# untitled.net
KiCad netlist of a schematic drawn in EAGLE
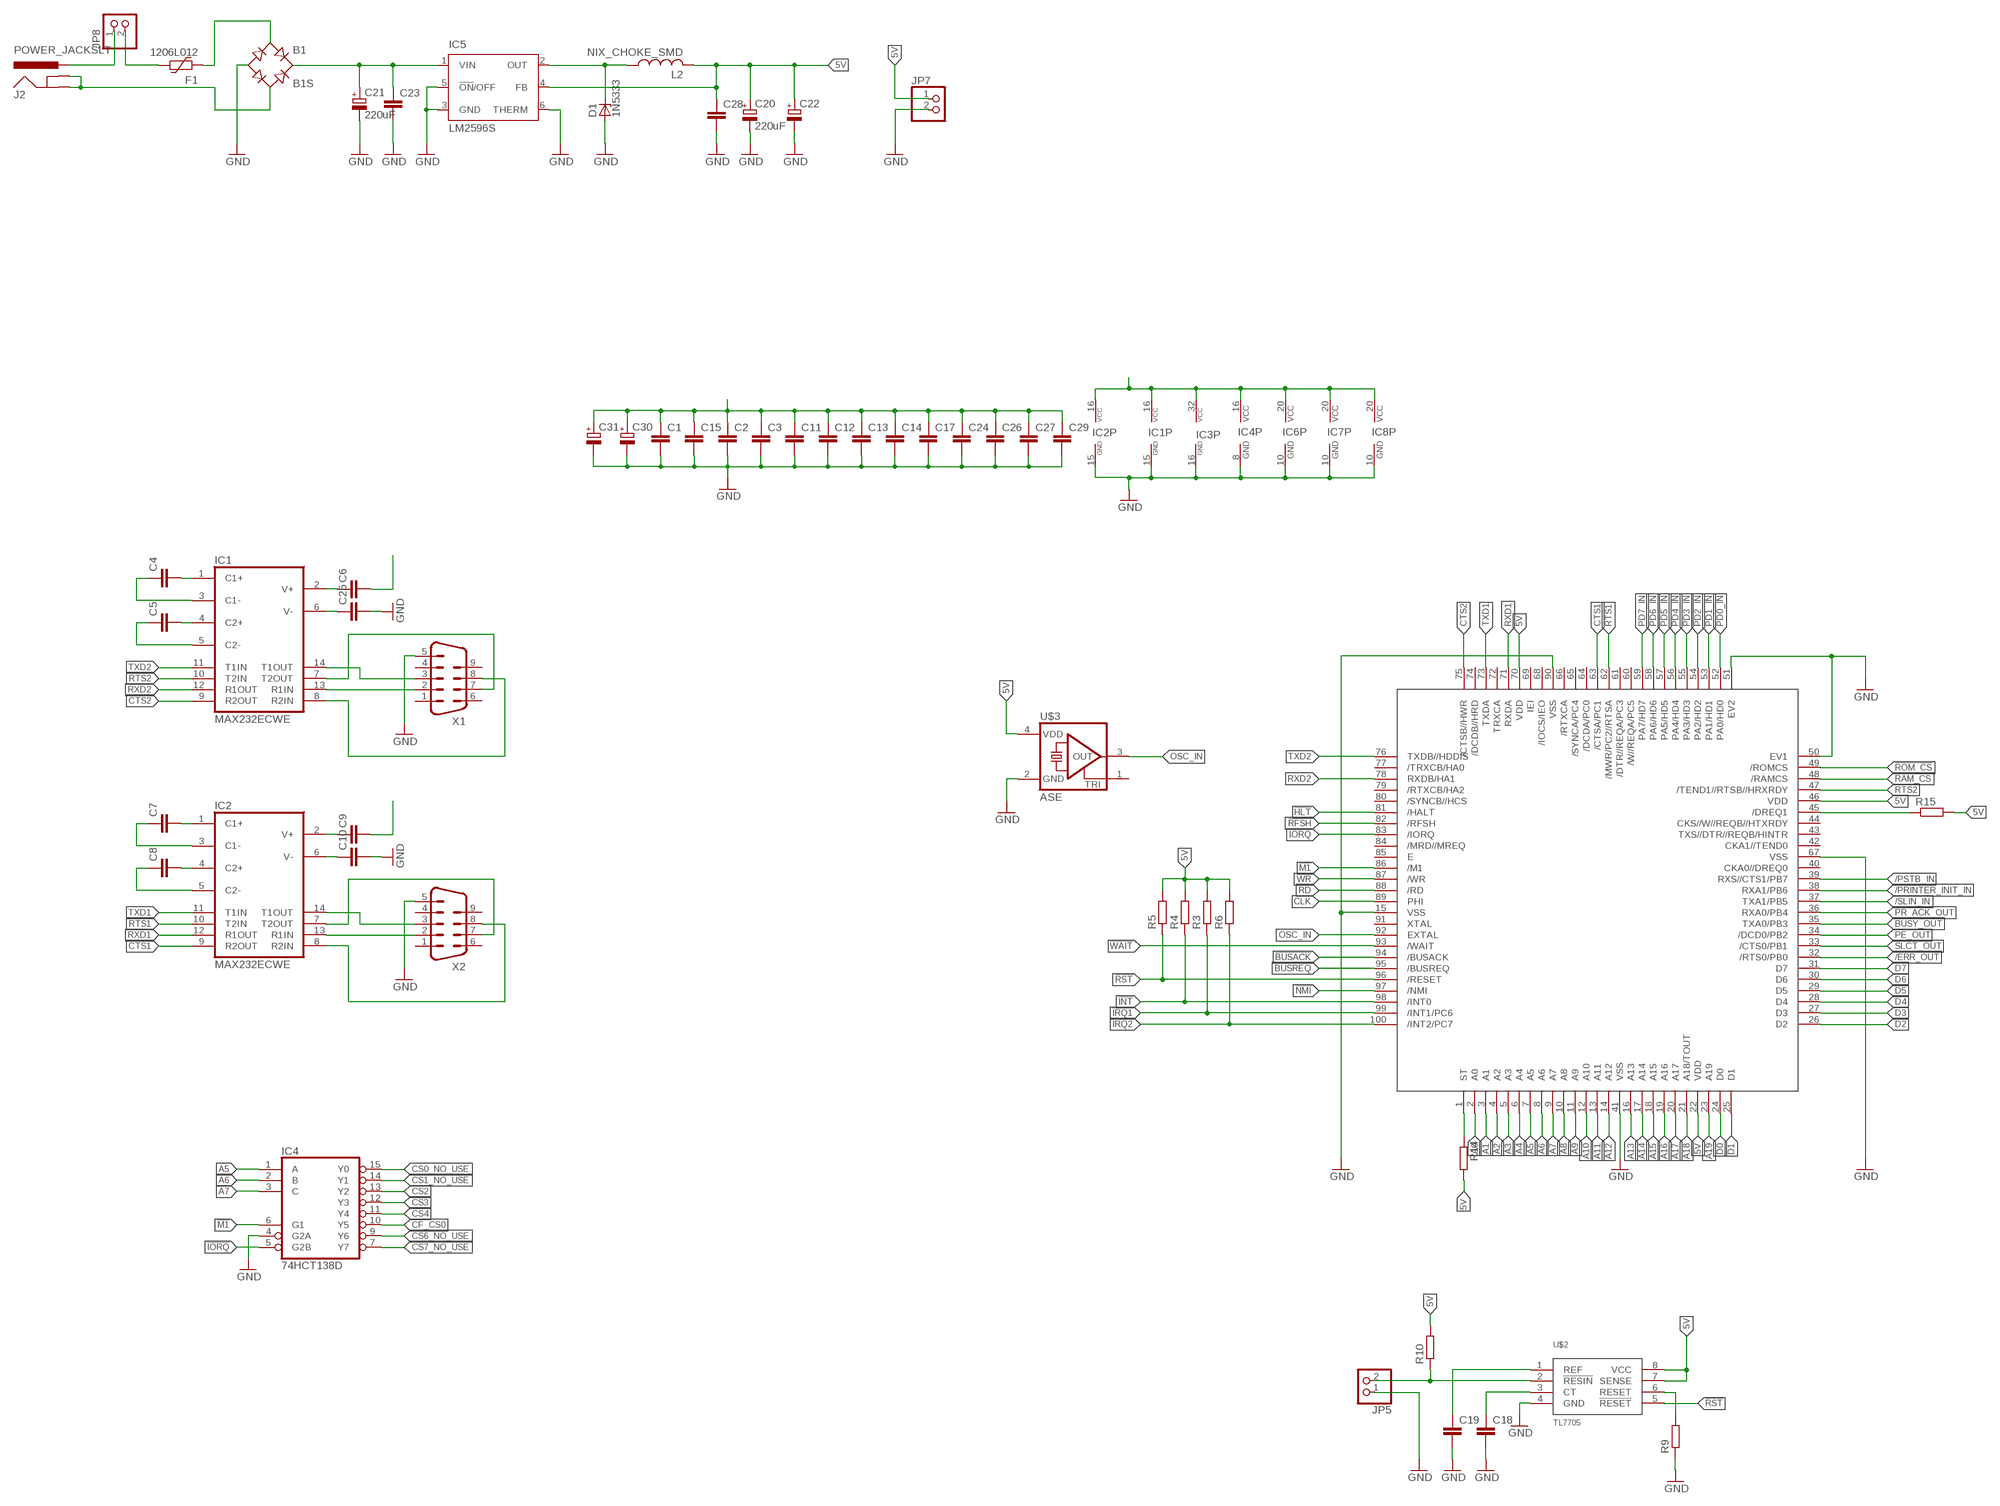
[diagram p0: schematic, sheet 1, part 1 of 2]
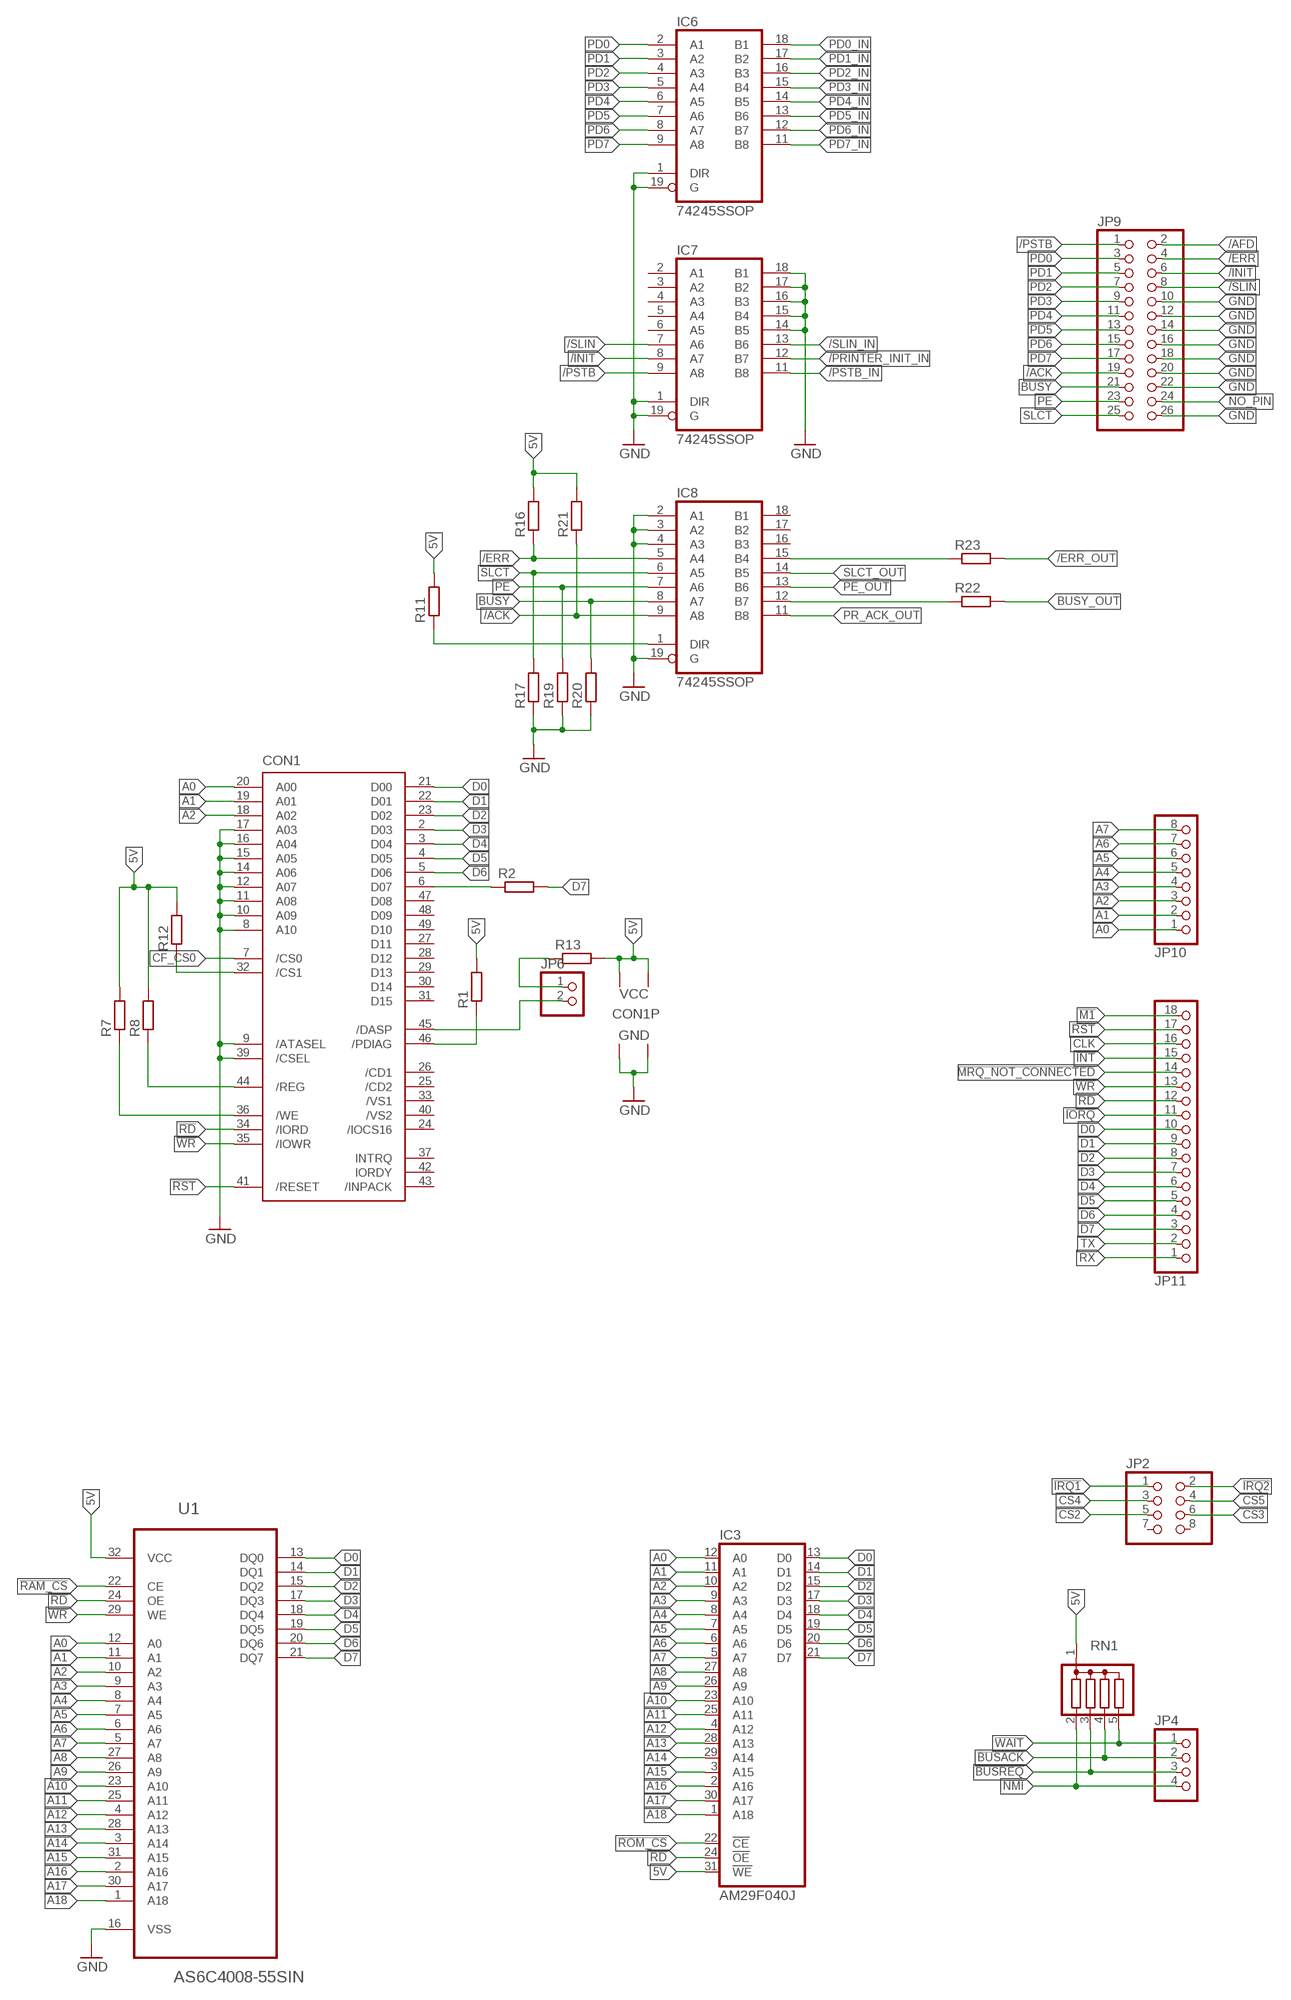
[diagram p1: schematic, sheet 1, part 2 of 2]

(export (version "E")
  (design (tool "Eeschema 10.0.6"))
  (components
    (comp (ref "B1")
      (value "B1S")
      (footprint "eagle-import:MBS")
      (libsource (lib "eagle-import") (part "BS1"))
    )
    (comp (ref "C1")
      (value "C-EUC0603")
      (footprint "eagle-import:C0603")
      (libsource (lib "eagle-import") (part "C-EUC0603"))
    )
    (comp (ref "C2")
      (value "C-EUC0603")
      (footprint "eagle-import:C0603")
      (libsource (lib "eagle-import") (part "C-EUC0603"))
    )
    (comp (ref "C3")
      (value "C-EUC0402")
      (footprint "eagle-import:C0402")
      (libsource (lib "eagle-import") (part "C-EUC0402"))
    )
    (comp (ref "C4")
      (value "C-EUC0603")
      (footprint "eagle-import:C0603")
      (libsource (lib "eagle-import") (part "C-EUC0603"))
    )
    (comp (ref "C5")
      (value "C-EUC0603")
      (footprint "eagle-import:C0603")
      (libsource (lib "eagle-import") (part "C-EUC0603"))
    )
    (comp (ref "C6")
      (value "C-EUC0603")
      (footprint "eagle-import:C0603")
      (libsource (lib "eagle-import") (part "C-EUC0603"))
    )
    (comp (ref "C7")
      (value "C-EUC0603")
      (footprint "eagle-import:C0603")
      (libsource (lib "eagle-import") (part "C-EUC0603"))
    )
    (comp (ref "C8")
      (value "C-EUC0603")
      (footprint "eagle-import:C0603")
      (libsource (lib "eagle-import") (part "C-EUC0603"))
    )
    (comp (ref "C9")
      (value "C-EUC0603")
      (footprint "eagle-import:C0603")
      (libsource (lib "eagle-import") (part "C-EUC0603"))
    )
    (comp (ref "C10")
      (value "C-EUC0603")
      (footprint "eagle-import:C0603")
      (libsource (lib "eagle-import") (part "C-EUC0603"))
    )
    (comp (ref "C11")
      (value "C-EUC0603")
      (footprint "eagle-import:C0603")
      (libsource (lib "eagle-import") (part "C-EUC0603"))
    )
    (comp (ref "C12")
      (value "C-EUC0603")
      (footprint "eagle-import:C0603")
      (libsource (lib "eagle-import") (part "C-EUC0603"))
    )
    (comp (ref "C13")
      (value "C-EUC0402")
      (footprint "eagle-import:C0402")
      (libsource (lib "eagle-import") (part "C-EUC0402"))
    )
    (comp (ref "C14")
      (value "C-EUC0603")
      (footprint "eagle-import:C0603")
      (libsource (lib "eagle-import") (part "C-EUC0603"))
    )
    (comp (ref "C15")
      (value "C-EUC0603")
      (footprint "eagle-import:C0603")
      (libsource (lib "eagle-import") (part "C-EUC0603"))
    )
    (comp (ref "C17")
      (value "C-EUC0603")
      (footprint "eagle-import:C0603")
      (libsource (lib "eagle-import") (part "C-EUC0603"))
    )
    (comp (ref "C18")
      (value "C-EUC0603")
      (footprint "eagle-import:C0603")
      (libsource (lib "eagle-import") (part "C-EUC0603"))
    )
    (comp (ref "C19")
      (value "C-EUC0603")
      (footprint "eagle-import:C0603")
      (libsource (lib "eagle-import") (part "C-EUC0603"))
    )
    (comp (ref "C20")
      (value "220uF")
      (footprint "eagle-import:153CLV-0810")
      (libsource (lib "eagle-import") (part "CPOL-EU153CLV-0810"))
    )
    (comp (ref "C21")
      (value "220uF")
      (footprint "eagle-import:153CLV-0810")
      (libsource (lib "eagle-import") (part "CPOL-EU153CLV-0810"))
    )
    (comp (ref "C22")
      (value "CPOL-EUSMCC")
      (footprint "eagle-import:SMC_C")
      (libsource (lib "eagle-import") (part "CPOL-EUSMCC"))
    )
    (comp (ref "C23")
      (value "C-EUC0603")
      (footprint "eagle-import:C0603")
      (libsource (lib "eagle-import") (part "C-EUC0603"))
    )
    (comp (ref "C24")
      (value "C-EUC0603")
      (footprint "eagle-import:C0603")
      (libsource (lib "eagle-import") (part "C-EUC0603"))
    )
    (comp (ref "C25")
      (value "C-EUC0603")
      (footprint "eagle-import:C0603")
      (libsource (lib "eagle-import") (part "C-EUC0603"))
    )
    (comp (ref "C26")
      (value "C-EUC0402")
      (footprint "eagle-import:C0402")
      (libsource (lib "eagle-import") (part "C-EUC0402"))
    )
    (comp (ref "C27")
      (value "C-EUC0402")
      (footprint "eagle-import:C0402")
      (libsource (lib "eagle-import") (part "C-EUC0402"))
    )
    (comp (ref "C28")
      (value "C-EUC0603")
      (footprint "eagle-import:C0603")
      (libsource (lib "eagle-import") (part "C-EUC0603"))
    )
    (comp (ref "C29")
      (value "C-EUC0603")
      (footprint "eagle-import:C0603")
      (libsource (lib "eagle-import") (part "C-EUC0603"))
    )
    (comp (ref "C30")
      (value "CPOL-EUSMCB")
      (footprint "eagle-import:SMC_B")
      (libsource (lib "eagle-import") (part "CPOL-EUSMCB"))
    )
    (comp (ref "C31")
      (value "CPOL-EUSMCB")
      (footprint "eagle-import:SMC_B")
      (libsource (lib "eagle-import") (part "CPOL-EUSMCB"))
    )
    (comp (ref "CON1")
      (value "CF-CARD-IDE_MODE")
      (footprint "eagle-import:MI20-50PD-SF")
      (libsource (lib "eagle-import") (part "CF-CARD-IDE_MODE"))
    )
    (comp (ref "D1")
      (value "1N5333")
      (footprint "eagle-import:C1702-15")
      (libsource (lib "eagle-import") (part "1N5333"))
    )
    (comp (ref "F1")
      (value "1206L012")
      (footprint "eagle-import:1206L")
      (fields (field (name "MF") "Littelfuse"))
      (libsource (lib "eagle-import") (part "?1206L012"))
    )
    (comp (ref "IC1")
      (value "MAX232ECWE")
      (footprint "eagle-import:SO16L")
      (fields (field (name "MF") "MAXIM") (field (name "MPN") "MAX232ECWE+"))
      (libsource (lib "eagle-import") (part "MAX232ECWE"))
    )
    (comp (ref "IC2")
      (value "MAX232ECWE")
      (footprint "eagle-import:SO16L")
      (fields (field (name "MF") "MAXIM") (field (name "MPN") "MAX232ECWE+"))
      (libsource (lib "eagle-import") (part "MAX232ECWE"))
    )
    (comp (ref "IC3")
      (value "AM29F040J")
      (footprint "eagle-import:PLCC32R")
      (libsource (lib "eagle-import") (part "AM29F040J"))
    )
    (comp (ref "IC4")
      (value "74HCT138D")
      (footprint "eagle-import:SO16")
      (libsource (lib "eagle-import") (part "74138DHCT"))
    )
    (comp (ref "IC5")
      (value "LM2596S")
      (footprint "eagle-import:TO263-5")
      (fields (field (name "MF") "NATIONAL SEMICONDUCTOR") (field (name "MPN") "LM2596S-ADJ/NOPB"))
      (libsource (lib "eagle-import") (part "LM2596S"))
    )
    (comp (ref "IC6")
      (value "74245SSOP")
      (footprint "eagle-import:SSOP20")
      (libsource (lib "eagle-import") (part "74245SSOP"))
    )
    (comp (ref "IC7")
      (value "74245SSOP")
      (footprint "eagle-import:SSOP20")
      (libsource (lib "eagle-import") (part "74245SSOP"))
    )
    (comp (ref "IC8")
      (value "74245SSOP")
      (footprint "eagle-import:SSOP20")
      (libsource (lib "eagle-import") (part "74245SSOP"))
    )
    (comp (ref "J2")
      (value "POWER_JACKSLT")
      (footprint "eagle-import:POWER_JACK_SLOT")
      (libsource (lib "eagle-import") (part "POWER_JACKSLT"))
    )
    (comp (ref "JP2")
      (value "PINHD-2X4")
      (footprint "eagle-import:2X04")
      (libsource (lib "eagle-import") (part "PINHD-2X4"))
    )
    (comp (ref "JP4")
      (value "PINHD-1X4")
      (footprint "eagle-import:1X04")
      (libsource (lib "eagle-import") (part "PINHD-1X4"))
    )
    (comp (ref "JP5")
      (value "PINHD-1X2")
      (footprint "eagle-import:1X02")
      (libsource (lib "eagle-import") (part "PINHD-1X2"))
    )
    (comp (ref "JP6")
      (value "PINHD-1X2")
      (footprint "eagle-import:1X02")
      (libsource (lib "eagle-import") (part "PINHD-1X2"))
    )
    (comp (ref "JP7")
      (value "PINHD-1X2")
      (footprint "eagle-import:1X02")
      (libsource (lib "eagle-import") (part "PINHD-1X2"))
    )
    (comp (ref "JP8")
      (value "PINHD-1X2")
      (footprint "eagle-import:1X02")
      (libsource (lib "eagle-import") (part "PINHD-1X2"))
    )
    (comp (ref "JP9")
      (value "PINHD-2X13_2.54-SMD")
      (footprint "eagle-import:2X13SMD")
      (libsource (lib "eagle-import") (part "PINHD-2X13_2.54-SMD"))
    )
    (comp (ref "JP10")
      (value "PINHD-1X8")
      (footprint "eagle-import:1X08")
      (libsource (lib "eagle-import") (part "PINHD-1X8"))
    )
    (comp (ref "JP11")
      (value "PINHD-1X18")
      (footprint "eagle-import:1X18")
      (libsource (lib "eagle-import") (part "PINHD-1X18"))
    )
    (comp (ref "L2")
      (value "NIX_CHOKE_SMD")
      (footprint "eagle-import:NIX_CHOKE_SMD")
      (libsource (lib "eagle-import") (part "NIX_CHOKE_SMD"))
    )
    (comp (ref "R1")
      (value "R-EU_R0603")
      (footprint "eagle-import:R0603")
      (libsource (lib "eagle-import") (part "R-EU_R0603"))
    )
    (comp (ref "R2")
      (value "R-EU_R0603")
      (footprint "eagle-import:R0603")
      (libsource (lib "eagle-import") (part "R-EU_R0603"))
    )
    (comp (ref "R3")
      (value "R-EU_R0402")
      (footprint "eagle-import:R0402")
      (libsource (lib "eagle-import") (part "R-EU_R0402"))
    )
    (comp (ref "R4")
      (value "R-EU_R0603")
      (footprint "eagle-import:R0603")
      (libsource (lib "eagle-import") (part "R-EU_R0603"))
    )
    (comp (ref "R5")
      (value "R-EU_R1206")
      (footprint "eagle-import:R1206")
      (libsource (lib "eagle-import") (part "R-EU_R1206"))
    )
    (comp (ref "R6")
      (value "R-EU_R0603")
      (footprint "eagle-import:R0603")
      (libsource (lib "eagle-import") (part "R-EU_R0603"))
    )
    (comp (ref "R7")
      (value "R-EU_R0603")
      (footprint "eagle-import:R0603")
      (libsource (lib "eagle-import") (part "R-EU_R0603"))
    )
    (comp (ref "R8")
      (value "R-EU_R0603")
      (footprint "eagle-import:R0603")
      (libsource (lib "eagle-import") (part "R-EU_R0603"))
    )
    (comp (ref "R9")
      (value "R-EU_R0603")
      (footprint "eagle-import:R0603")
      (libsource (lib "eagle-import") (part "R-EU_R0603"))
    )
    (comp (ref "R10")
      (value "R-EU_M1206")
      (footprint "eagle-import:M1206")
      (libsource (lib "eagle-import") (part "R-EU_M1206"))
    )
    (comp (ref "R11")
      (value "R-EU_R0603")
      (footprint "eagle-import:R0603")
      (libsource (lib "eagle-import") (part "R-EU_R0603"))
    )
    (comp (ref "R12")
      (value "R-EU_R0603")
      (footprint "eagle-import:R0603")
      (libsource (lib "eagle-import") (part "R-EU_R0603"))
    )
    (comp (ref "R13")
      (value "R-EU_R0603")
      (footprint "eagle-import:R0603")
      (libsource (lib "eagle-import") (part "R-EU_R0603"))
    )
    (comp (ref "R14")
      (value "R-EU_0204/5")
      (footprint "eagle-import:0204_5")
      (libsource (lib "eagle-import") (part "R-EU_0204/5"))
    )
    (comp (ref "R15")
      (value "R-EU_R0402")
      (footprint "eagle-import:R0402")
      (libsource (lib "eagle-import") (part "R-EU_R0402"))
    )
    (comp (ref "R16")
      (value "R-EU_R0603")
      (footprint "eagle-import:R0603")
      (libsource (lib "eagle-import") (part "R-EU_R0603"))
    )
    (comp (ref "R17")
      (value "R-EU_R0603")
      (footprint "eagle-import:R0603")
      (libsource (lib "eagle-import") (part "R-EU_R0603"))
    )
    (comp (ref "R19")
      (value "R-EU_R0603")
      (footprint "eagle-import:R0603")
      (libsource (lib "eagle-import") (part "R-EU_R0603"))
    )
    (comp (ref "R20")
      (value "R-EU_R0603")
      (footprint "eagle-import:R0603")
      (libsource (lib "eagle-import") (part "R-EU_R0603"))
    )
    (comp (ref "R21")
      (value "R-EU_R0603")
      (footprint "eagle-import:R0603")
      (libsource (lib "eagle-import") (part "R-EU_R0603"))
    )
    (comp (ref "R22")
      (value "R-EU_R0402")
      (footprint "eagle-import:R0402")
      (libsource (lib "eagle-import") (part "R-EU_R0402"))
    )
    (comp (ref "R23")
      (value "R-EU_R0402")
      (footprint "eagle-import:R0402")
      (libsource (lib "eagle-import") (part "R-EU_R0402"))
    )
    (comp (ref "RN1")
      (value "G04R")
      (footprint "eagle-import:SIL5")
      (libsource (lib "eagle-import") (part "G04R"))
    )
    (comp (ref "U$1")
      (value "Z80182")
      (footprint "eagle-import:TQFP100")
      (libsource (lib "eagle-import") (part "Z80182"))
    )
    (comp (ref "U$2")
      (value "TL7705")
      (footprint "eagle-import:SOIC8")
      (libsource (lib "eagle-import") (part "TL7705"))
    )
    (comp (ref "U$3")
      (value "ASE")
      (footprint "eagle-import:ASE")
      (libsource (lib "eagle-import") (part "ASE"))
    )
    (comp (ref "U1")
      (value "AS6C4008-55SIN")
      (footprint "eagle-import:SOIC127P1407X299-32N")
      (libsource (lib "eagle-import") (part "AS6C4008-55SIN"))
    )
    (comp (ref "X1")
      (value "M09HP")
      (footprint "eagle-import:M09HP")
      (libsource (lib "eagle-import") (part "M09HP"))
    )
    (comp (ref "X2")
      (value "M09HP")
      (footprint "eagle-import:M09HP")
      (libsource (lib "eagle-import") (part "M09HP"))
    )
  )
  (nets
    (net (code "1") (name "/~{BUSACK}") (class "Default")
      (node (ref "JP4") (pin "2") (pinfunction "2_2") (pintype "passive"))
      (node (ref "RN1") (pin "4") (pinfunction "4_4") (pintype "passive"))
      (node (ref "U$1") (pin "94") (pinfunction "/BUSACK_94") (pintype "bidirectional"))
    )
    (net (code "2") (name "/~{BUSREQ}") (class "Default")
      (node (ref "JP4") (pin "3") (pinfunction "3_3") (pintype "passive"))
      (node (ref "RN1") (pin "3") (pinfunction "3_3") (pintype "passive"))
      (node (ref "U$1") (pin "95") (pinfunction "/BUSREQ_95") (pintype "bidirectional"))
    )
    (net (code "3") (name "/~{HLT}") (class "Default")
      (node (ref "U$1") (pin "81") (pinfunction "/HALT_81") (pintype "bidirectional"))
    )
    (net (code "4") (name "/~{INT}") (class "Default")
      (node (ref "JP11") (pin "15") (pinfunction "15_15") (pintype "passive"))
      (node (ref "R4") (pin "1") (pinfunction "1_1") (pintype "passive"))
      (node (ref "U$1") (pin "98") (pinfunction "/INT0_98") (pintype "bidirectional"))
    )
    (net (code "5") (name "/~{IORQ}") (class "Default")
      (node (ref "IC4") (pin "5") (pinfunction "G2B_5") (pintype "input"))
      (node (ref "JP11") (pin "11") (pinfunction "11_11") (pintype "passive"))
      (node (ref "U$1") (pin "83") (pinfunction "/IORQ_83") (pintype "bidirectional"))
    )
    (net (code "6") (name "/~{IRQ1}") (class "Default")
      (node (ref "JP2") (pin "1") (pinfunction "1_1") (pintype "passive"))
      (node (ref "R3") (pin "1") (pinfunction "1_1") (pintype "passive"))
      (node (ref "U$1") (pin "99") (pinfunction "/INT1/PC6_99") (pintype "bidirectional"))
    )
    (net (code "7") (name "/~{IRQ2}") (class "Default")
      (node (ref "JP2") (pin "2") (pinfunction "2_2") (pintype "passive"))
      (node (ref "R6") (pin "1") (pinfunction "1_1") (pintype "passive"))
      (node (ref "U$1") (pin "100") (pinfunction "/INT2/PC7_100") (pintype "bidirectional"))
    )
    (net (code "8") (name "/~{M1}") (class "Default")
      (node (ref "IC4") (pin "6") (pinfunction "G1_6") (pintype "input"))
      (node (ref "JP11") (pin "18") (pinfunction "18_18") (pintype "passive"))
      (node (ref "U$1") (pin "86") (pinfunction "/M1_86") (pintype "bidirectional"))
    )
    (net (code "9") (name "/~{MRQ_NOT_CONNECTED}") (class "Default")
      (node (ref "JP11") (pin "14") (pinfunction "14_14") (pintype "passive"))
    )
    (net (code "10") (name "/~{NMI}") (class "Default")
      (node (ref "JP4") (pin "4") (pinfunction "4_4") (pintype "passive"))
      (node (ref "RN1") (pin "2") (pinfunction "2_2") (pintype "passive"))
      (node (ref "U$1") (pin "97") (pinfunction "/NMI_97") (pintype "bidirectional"))
    )
    (net (code "11") (name "/~{RAM_CS}") (class "Default")
      (node (ref "U$1") (pin "48") (pinfunction "/RAMCS_48") (pintype "bidirectional"))
      (node (ref "U1") (pin "22") (pinfunction "CE_22") (pintype "input"))
    )
    (net (code "12") (name "/~{RD}") (class "Default")
      (node (ref "CON1") (pin "34") (pinfunction "/IORD_34") (pintype "input"))
      (node (ref "IC3") (pin "24") (pinfunction "~{OE}_24") (pintype "input"))
      (node (ref "JP11") (pin "12") (pinfunction "12_12") (pintype "passive"))
      (node (ref "U$1") (pin "88") (pinfunction "/RD_88") (pintype "bidirectional"))
      (node (ref "U1") (pin "24") (pinfunction "OE_24") (pintype "input"))
    )
    (net (code "13") (name "/~{RFSH}") (class "Default")
      (node (ref "U$1") (pin "82") (pinfunction "/RFSH_82") (pintype "bidirectional"))
    )
    (net (code "14") (name "/~{ROM_CS}") (class "Default")
      (node (ref "IC3") (pin "22") (pinfunction "~{CE}_22") (pintype "input"))
      (node (ref "U$1") (pin "49") (pinfunction "/ROMCS_49") (pintype "bidirectional"))
    )
    (net (code "15") (name "/~{RST}") (class "Default")
      (node (ref "CON1") (pin "41") (pinfunction "/RESET_41") (pintype "input"))
      (node (ref "JP11") (pin "17") (pinfunction "17_17") (pintype "passive"))
      (node (ref "R5") (pin "1") (pinfunction "1_1") (pintype "passive"))
      (node (ref "U$1") (pin "96") (pinfunction "/RESET_96") (pintype "bidirectional"))
      (node (ref "U$2") (pin "5") (pinfunction "~{RESET}_5") (pintype "bidirectional"))
    )
    (net (code "16") (name "/~{WAIT}") (class "Default")
      (node (ref "JP4") (pin "1") (pinfunction "1_1") (pintype "passive"))
      (node (ref "RN1") (pin "5") (pinfunction "5_5") (pintype "passive"))
      (node (ref "U$1") (pin "93") (pinfunction "/WAIT_93") (pintype "bidirectional"))
    )
    (net (code "17") (name "/~{WR}") (class "Default")
      (node (ref "CON1") (pin "35") (pinfunction "/IOWR_35") (pintype "input"))
      (node (ref "JP11") (pin "13") (pinfunction "13_13") (pintype "passive"))
      (node (ref "U$1") (pin "87") (pinfunction "/WR_87") (pintype "bidirectional"))
      (node (ref "U1") (pin "29") (pinfunction "WE_29") (pintype "input"))
    )
    (net (code "18") (name "5V") (class "Default")
      (node (ref "C1") (pin "1") (pinfunction "1_1") (pintype "passive"))
      (node (ref "C11") (pin "1") (pinfunction "1_1") (pintype "passive"))
      (node (ref "C12") (pin "1") (pinfunction "1_1") (pintype "passive"))
      (node (ref "C13") (pin "1") (pinfunction "1_1") (pintype "passive"))
      (node (ref "C14") (pin "1") (pinfunction "1_1") (pintype "passive"))
      (node (ref "C15") (pin "1") (pinfunction "1_1") (pintype "passive"))
      (node (ref "C17") (pin "1") (pinfunction "1_1") (pintype "passive"))
      (node (ref "C2") (pin "1") (pinfunction "1_1") (pintype "passive"))
      (node (ref "C20") (pin "+") (pinfunction "+_+") (pintype "passive"))
      (node (ref "C22") (pin "+") (pinfunction "+_+") (pintype "passive"))
      (node (ref "C24") (pin "1") (pinfunction "1_1") (pintype "passive"))
      (node (ref "C26") (pin "1") (pinfunction "1_1") (pintype "passive"))
      (node (ref "C27") (pin "1") (pinfunction "1_1") (pintype "passive"))
      (node (ref "C28") (pin "1") (pinfunction "1_1") (pintype "passive"))
      (node (ref "C29") (pin "1") (pinfunction "1_1") (pintype "passive"))
      (node (ref "C3") (pin "1") (pinfunction "1_1") (pintype "passive"))
      (node (ref "C30") (pin "+") (pinfunction "+_+") (pintype "passive"))
      (node (ref "C31") (pin "+") (pinfunction "+_+") (pintype "passive"))
      (node (ref "C6") (pin "2") (pinfunction "2_2") (pintype "passive"))
      (node (ref "C9") (pin "2") (pinfunction "2_2") (pintype "passive"))
      (node (ref "CON1") (pin "13") (pinfunction "VCC2_13") (pintype "power_in"))
      (node (ref "CON1") (pin "38") (pinfunction "VCC1_38") (pintype "power_in"))
      (node (ref "IC1") (pin "16") (pinfunction "VCC_16") (pintype "power_in"))
      (node (ref "IC2") (pin "16") (pinfunction "VCC_16") (pintype "power_in"))
      (node (ref "IC3") (pin "31") (pinfunction "~{WE}_31") (pintype "input"))
      (node (ref "IC3") (pin "32") (pinfunction "VCC_32") (pintype "power_in"))
      (node (ref "IC4") (pin "16") (pinfunction "VCC_16") (pintype "power_in"))
      (node (ref "IC5") (pin "4") (pinfunction "FB_4") (pintype "input"))
      (node (ref "IC6") (pin "20") (pinfunction "VCC_20") (pintype "power_in"))
      (node (ref "IC7") (pin "20") (pinfunction "VCC_20") (pintype "power_in"))
      (node (ref "IC8") (pin "20") (pinfunction "VCC_20") (pintype "power_in"))
      (node (ref "JP7") (pin "1") (pinfunction "1_1") (pintype "passive"))
      (node (ref "L2") (pin "P$2") (pinfunction "2_P$2") (pintype "passive"))
      (node (ref "R1") (pin "2") (pinfunction "2_2") (pintype "passive"))
      (node (ref "R10") (pin "2") (pinfunction "2_2") (pintype "passive"))
      (node (ref "R11") (pin "2") (pinfunction "2_2") (pintype "passive"))
      (node (ref "R12") (pin "2") (pinfunction "2_2") (pintype "passive"))
      (node (ref "R13") (pin "2") (pinfunction "2_2") (pintype "passive"))
      (node (ref "R14") (pin "2") (pinfunction "2_2") (pintype "passive"))
      (node (ref "R15") (pin "2") (pinfunction "2_2") (pintype "passive"))
      (node (ref "R16") (pin "2") (pinfunction "2_2") (pintype "passive"))
      (node (ref "R21") (pin "2") (pinfunction "2_2") (pintype "passive"))
      (node (ref "R3") (pin "2") (pinfunction "2_2") (pintype "passive"))
      (node (ref "R4") (pin "2") (pinfunction "2_2") (pintype "passive"))
      (node (ref "R5") (pin "2") (pinfunction "2_2") (pintype "passive"))
      (node (ref "R6") (pin "2") (pinfunction "2_2") (pintype "passive"))
      (node (ref "R7") (pin "2") (pinfunction "2_2") (pintype "passive"))
      (node (ref "R8") (pin "2") (pinfunction "2_2") (pintype "passive"))
      (node (ref "RN1") (pin "1") (pinfunction "1_1") (pintype "passive"))
      (node (ref "U$1") (pin "22") (pinfunction "VDD_22") (pintype "bidirectional"))
      (node (ref "U$1") (pin "46") (pinfunction "VDD_46") (pintype "bidirectional"))
      (node (ref "U$1") (pin "70") (pinfunction "VDD_70") (pintype "bidirectional"))
      (node (ref "U$2") (pin "7") (pinfunction "SENSE_7") (pintype "bidirectional"))
      (node (ref "U$2") (pin "8") (pinfunction "VCC_8") (pintype "bidirectional"))
      (node (ref "U$3") (pin "4") (pinfunction "VDD_4") (pintype "power_in"))
      (node (ref "U1") (pin "32") (pinfunction "VCC_32") (pintype "power_in"))
    )
    (net (code "19") (name "A0") (class "Default")
      (node (ref "CON1") (pin "20") (pinfunction "A00_20") (pintype "input"))
      (node (ref "IC3") (pin "12") (pinfunction "A0_12") (pintype "input"))
      (node (ref "JP10") (pin "1") (pinfunction "1_1") (pintype "passive"))
      (node (ref "U$1") (pin "2") (pinfunction "A0_2") (pintype "bidirectional"))
      (node (ref "U1") (pin "12") (pinfunction "A0_12") (pintype "input"))
    )
    (net (code "20") (name "A1") (class "Default")
      (node (ref "CON1") (pin "19") (pinfunction "A01_19") (pintype "input"))
      (node (ref "IC3") (pin "11") (pinfunction "A1_11") (pintype "input"))
      (node (ref "JP10") (pin "2") (pinfunction "2_2") (pintype "passive"))
      (node (ref "U$1") (pin "3") (pinfunction "A1_3") (pintype "bidirectional"))
      (node (ref "U1") (pin "11") (pinfunction "A1_11") (pintype "input"))
    )
    (net (code "21") (name "A2") (class "Default")
      (node (ref "CON1") (pin "18") (pinfunction "A02_18") (pintype "input"))
      (node (ref "IC3") (pin "10") (pinfunction "A2_10") (pintype "input"))
      (node (ref "JP10") (pin "3") (pinfunction "3_3") (pintype "passive"))
      (node (ref "U$1") (pin "4") (pinfunction "A2_4") (pintype "bidirectional"))
      (node (ref "U1") (pin "10") (pinfunction "A2_10") (pintype "input"))
    )
    (net (code "22") (name "A3") (class "Default")
      (node (ref "IC3") (pin "9") (pinfunction "A3_9") (pintype "input"))
      (node (ref "JP10") (pin "4") (pinfunction "4_4") (pintype "passive"))
      (node (ref "U$1") (pin "5") (pinfunction "A3_5") (pintype "bidirectional"))
      (node (ref "U1") (pin "9") (pinfunction "A3_9") (pintype "input"))
    )
    (net (code "23") (name "A4") (class "Default")
      (node (ref "IC3") (pin "8") (pinfunction "A4_8") (pintype "input"))
      (node (ref "JP10") (pin "5") (pinfunction "5_5") (pintype "passive"))
      (node (ref "U$1") (pin "6") (pinfunction "A4_6") (pintype "bidirectional"))
      (node (ref "U1") (pin "8") (pinfunction "A4_8") (pintype "input"))
    )
    (net (code "24") (name "A5") (class "Default")
      (node (ref "IC3") (pin "7") (pinfunction "A5_7") (pintype "input"))
      (node (ref "IC4") (pin "1") (pinfunction "A_1") (pintype "input"))
      (node (ref "JP10") (pin "6") (pinfunction "6_6") (pintype "passive"))
      (node (ref "U$1") (pin "7") (pinfunction "A5_7") (pintype "bidirectional"))
      (node (ref "U1") (pin "7") (pinfunction "A5_7") (pintype "input"))
    )
    (net (code "25") (name "A6") (class "Default")
      (node (ref "IC3") (pin "6") (pinfunction "A6_6") (pintype "input"))
      (node (ref "IC4") (pin "2") (pinfunction "B_2") (pintype "input"))
      (node (ref "JP10") (pin "7") (pinfunction "7_7") (pintype "passive"))
      (node (ref "U$1") (pin "8") (pinfunction "A6_8") (pintype "bidirectional"))
      (node (ref "U1") (pin "6") (pinfunction "A6_6") (pintype "input"))
    )
    (net (code "26") (name "A7") (class "Default")
      (node (ref "IC3") (pin "5") (pinfunction "A7_5") (pintype "input"))
      (node (ref "IC4") (pin "3") (pinfunction "C_3") (pintype "input"))
      (node (ref "JP10") (pin "8") (pinfunction "8_8") (pintype "passive"))
      (node (ref "U$1") (pin "9") (pinfunction "A7_9") (pintype "bidirectional"))
      (node (ref "U1") (pin "5") (pinfunction "A7_5") (pintype "input"))
    )
    (net (code "27") (name "A8") (class "Default")
      (node (ref "IC3") (pin "27") (pinfunction "A8_27") (pintype "input"))
      (node (ref "U$1") (pin "10") (pinfunction "A8_10") (pintype "bidirectional"))
      (node (ref "U1") (pin "27") (pinfunction "A8_27") (pintype "input"))
    )
    (net (code "28") (name "A9") (class "Default")
      (node (ref "IC3") (pin "26") (pinfunction "A9_26") (pintype "input"))
      (node (ref "U$1") (pin "11") (pinfunction "A9_11") (pintype "bidirectional"))
      (node (ref "U1") (pin "26") (pinfunction "A9_26") (pintype "input"))
    )
    (net (code "29") (name "A10") (class "Default")
      (node (ref "IC3") (pin "23") (pinfunction "A10_23") (pintype "input"))
      (node (ref "U$1") (pin "12") (pinfunction "A10_12") (pintype "bidirectional"))
      (node (ref "U1") (pin "23") (pinfunction "A10_23") (pintype "input"))
    )
    (net (code "30") (name "A11") (class "Default")
      (node (ref "IC3") (pin "25") (pinfunction "A11_25") (pintype "input"))
      (node (ref "U$1") (pin "13") (pinfunction "A11_13") (pintype "bidirectional"))
      (node (ref "U1") (pin "25") (pinfunction "A11_25") (pintype "input"))
    )
    (net (code "31") (name "A12") (class "Default")
      (node (ref "IC3") (pin "4") (pinfunction "A12_4") (pintype "input"))
      (node (ref "U$1") (pin "14") (pinfunction "A12_14") (pintype "bidirectional"))
      (node (ref "U1") (pin "4") (pinfunction "A12_4") (pintype "input"))
    )
    (net (code "32") (name "A13") (class "Default")
      (node (ref "IC3") (pin "28") (pinfunction "A13_28") (pintype "input"))
      (node (ref "U$1") (pin "16") (pinfunction "A13_16") (pintype "bidirectional"))
      (node (ref "U1") (pin "28") (pinfunction "A13_28") (pintype "input"))
    )
    (net (code "33") (name "A14") (class "Default")
      (node (ref "IC3") (pin "29") (pinfunction "A14_29") (pintype "input"))
      (node (ref "U$1") (pin "17") (pinfunction "A14_17") (pintype "bidirectional"))
      (node (ref "U1") (pin "3") (pinfunction "A14_3") (pintype "input"))
    )
    (net (code "34") (name "A15") (class "Default")
      (node (ref "IC3") (pin "3") (pinfunction "A15_3") (pintype "input"))
      (node (ref "U$1") (pin "18") (pinfunction "A15_18") (pintype "bidirectional"))
      (node (ref "U1") (pin "31") (pinfunction "A15_31") (pintype "input"))
    )
    (net (code "35") (name "A16") (class "Default")
      (node (ref "IC3") (pin "2") (pinfunction "A16_2") (pintype "input"))
      (node (ref "U$1") (pin "19") (pinfunction "A16_19") (pintype "bidirectional"))
      (node (ref "U1") (pin "2") (pinfunction "A16_2") (pintype "input"))
    )
    (net (code "36") (name "A17") (class "Default")
      (node (ref "IC3") (pin "30") (pinfunction "A17_30") (pintype "input"))
      (node (ref "U$1") (pin "20") (pinfunction "A17_20") (pintype "bidirectional"))
      (node (ref "U1") (pin "30") (pinfunction "A17_30") (pintype "input"))
    )
    (net (code "37") (name "A18") (class "Default")
      (node (ref "IC3") (pin "1") (pinfunction "A18_1") (pintype "input"))
      (node (ref "U$1") (pin "21") (pinfunction "A18/TOUT_21") (pintype "bidirectional"))
      (node (ref "U1") (pin "1") (pinfunction "A18_1") (pintype "input"))
    )
    (net (code "38") (name "A19") (class "Default")
      (node (ref "U$1") (pin "23") (pinfunction "A19_23") (pintype "bidirectional"))
    )
    (net (code "39") (name "BUSY") (class "Default")
      (node (ref "IC8") (pin "8") (pinfunction "A7_8") (pintype "bidirectional"))
      (node (ref "JP9") (pin "21") (pinfunction "21_21") (pintype "passive"))
      (node (ref "R20") (pin "2") (pinfunction "2_2") (pintype "passive"))
    )
    (net (code "40") (name "BUSY_OUT") (class "Default")
      (node (ref "R22") (pin "2") (pinfunction "2_2") (pintype "passive"))
      (node (ref "U$1") (pin "35") (pinfunction "TXA0/PB3_35") (pintype "bidirectional"))
    )
    (net (code "41") (name "CF_CS0") (class "Default")
      (node (ref "CON1") (pin "7") (pinfunction "/CS0_7") (pintype "input"))
      (node (ref "IC4") (pin "10") (pinfunction "Y5_10") (pintype "output"))
    )
    (net (code "42") (name "CLK") (class "Default")
      (node (ref "JP11") (pin "16") (pinfunction "16_16") (pintype "passive"))
      (node (ref "U$1") (pin "89") (pinfunction "PHI_89") (pintype "bidirectional"))
    )
    (net (code "43") (name "CS0_NO_USE") (class "Default")
      (node (ref "IC4") (pin "15") (pinfunction "Y0_15") (pintype "output"))
    )
    (net (code "44") (name "CS1_NO_USE") (class "Default")
      (node (ref "IC4") (pin "14") (pinfunction "Y1_14") (pintype "output"))
    )
    (net (code "45") (name "CS2") (class "Default")
      (node (ref "IC4") (pin "13") (pinfunction "Y2_13") (pintype "output"))
      (node (ref "JP2") (pin "5") (pinfunction "5_5") (pintype "passive"))
    )
    (net (code "46") (name "CS3") (class "Default")
      (node (ref "IC4") (pin "12") (pinfunction "Y3_12") (pintype "output"))
      (node (ref "JP2") (pin "6") (pinfunction "6_6") (pintype "passive"))
    )
    (net (code "47") (name "CS4") (class "Default")
      (node (ref "IC4") (pin "11") (pinfunction "Y4_11") (pintype "output"))
      (node (ref "JP2") (pin "3") (pinfunction "3_3") (pintype "passive"))
    )
    (net (code "48") (name "CS5") (class "Default")
      (node (ref "JP2") (pin "4") (pinfunction "4_4") (pintype "passive"))
    )
    (net (code "49") (name "CS6_NO_USE") (class "Default")
      (node (ref "IC4") (pin "9") (pinfunction "Y6_9") (pintype "output"))
    )
    (net (code "50") (name "CS7_NO_USE") (class "Default")
      (node (ref "IC4") (pin "7") (pinfunction "Y7_7") (pintype "output"))
    )
    (net (code "51") (name "CTS1") (class "Default")
      (node (ref "IC2") (pin "9") (pinfunction "R2OUT_9") (pintype "output"))
      (node (ref "U$1") (pin "63") (pinfunction "/CTSA/PC1_63") (pintype "bidirectional"))
    )
    (net (code "52") (name "CTS2") (class "Default")
      (node (ref "IC1") (pin "9") (pinfunction "R2OUT_9") (pintype "output"))
      (node (ref "U$1") (pin "75") (pinfunction "/CTSB//HWR_75") (pintype "bidirectional"))
    )
    (net (code "53") (name "D0") (class "Default")
      (node (ref "CON1") (pin "21") (pinfunction "D00_21") (pintype "bidirectional"))
      (node (ref "IC3") (pin "13") (pinfunction "D0_13") (pintype "tri_state"))
      (node (ref "JP11") (pin "10") (pinfunction "10_10") (pintype "passive"))
      (node (ref "U$1") (pin "24") (pinfunction "D0_24") (pintype "bidirectional"))
      (node (ref "U1") (pin "13") (pinfunction "DQ0_13") (pintype "output"))
    )
    (net (code "54") (name "D1") (class "Default")
      (node (ref "CON1") (pin "22") (pinfunction "D01_22") (pintype "bidirectional"))
      (node (ref "IC3") (pin "14") (pinfunction "D1_14") (pintype "tri_state"))
      (node (ref "JP11") (pin "9") (pinfunction "9_9") (pintype "passive"))
      (node (ref "U$1") (pin "25") (pinfunction "D1_25") (pintype "bidirectional"))
      (node (ref "U1") (pin "14") (pinfunction "DQ1_14") (pintype "output"))
    )
    (net (code "55") (name "D2") (class "Default")
      (node (ref "CON1") (pin "23") (pinfunction "D02_23") (pintype "bidirectional"))
      (node (ref "IC3") (pin "15") (pinfunction "D2_15") (pintype "tri_state"))
      (node (ref "JP11") (pin "8") (pinfunction "8_8") (pintype "passive"))
      (node (ref "U$1") (pin "26") (pinfunction "D2_26") (pintype "bidirectional"))
      (node (ref "U1") (pin "15") (pinfunction "DQ2_15") (pintype "output"))
    )
    (net (code "56") (name "D3") (class "Default")
      (node (ref "CON1") (pin "2") (pinfunction "D03_2") (pintype "bidirectional"))
      (node (ref "IC3") (pin "17") (pinfunction "D3_17") (pintype "tri_state"))
      (node (ref "JP11") (pin "7") (pinfunction "7_7") (pintype "passive"))
      (node (ref "U$1") (pin "27") (pinfunction "D3_27") (pintype "bidirectional"))
      (node (ref "U1") (pin "17") (pinfunction "DQ3_17") (pintype "output"))
    )
    (net (code "57") (name "D4") (class "Default")
      (node (ref "CON1") (pin "3") (pinfunction "D04_3") (pintype "bidirectional"))
      (node (ref "IC3") (pin "18") (pinfunction "D4_18") (pintype "tri_state"))
      (node (ref "JP11") (pin "6") (pinfunction "6_6") (pintype "passive"))
      (node (ref "U$1") (pin "28") (pinfunction "D4_28") (pintype "bidirectional"))
      (node (ref "U1") (pin "18") (pinfunction "DQ4_18") (pintype "output"))
    )
    (net (code "58") (name "D5") (class "Default")
      (node (ref "CON1") (pin "4") (pinfunction "D05_4") (pintype "bidirectional"))
      (node (ref "IC3") (pin "19") (pinfunction "D5_19") (pintype "tri_state"))
      (node (ref "JP11") (pin "5") (pinfunction "5_5") (pintype "passive"))
      (node (ref "U$1") (pin "29") (pinfunction "D5_29") (pintype "bidirectional"))
      (node (ref "U1") (pin "19") (pinfunction "DQ5_19") (pintype "output"))
    )
    (net (code "59") (name "D6") (class "Default")
      (node (ref "CON1") (pin "5") (pinfunction "D06_5") (pintype "bidirectional"))
      (node (ref "IC3") (pin "20") (pinfunction "D6_20") (pintype "tri_state"))
      (node (ref "JP11") (pin "4") (pinfunction "4_4") (pintype "passive"))
      (node (ref "U$1") (pin "30") (pinfunction "D6_30") (pintype "bidirectional"))
      (node (ref "U1") (pin "20") (pinfunction "DQ6_20") (pintype "output"))
    )
    (net (code "60") (name "D7") (class "Default")
      (node (ref "IC3") (pin "21") (pinfunction "D7_21") (pintype "tri_state"))
      (node (ref "JP11") (pin "3") (pinfunction "3_3") (pintype "passive"))
      (node (ref "R2") (pin "2") (pinfunction "2_2") (pintype "passive"))
      (node (ref "U$1") (pin "31") (pinfunction "D7_31") (pintype "bidirectional"))
      (node (ref "U1") (pin "21") (pinfunction "DQ7_21") (pintype "output"))
    )
    (net (code "61") (name "GND") (class "Default")
      (node (ref "B1") (pin "-") (pinfunction "-_-") (pintype "passive"))
      (node (ref "C1") (pin "2") (pinfunction "2_2") (pintype "passive"))
      (node (ref "C10") (pin "2") (pinfunction "2_2") (pintype "passive"))
      (node (ref "C11") (pin "2") (pinfunction "2_2") (pintype "passive"))
      (node (ref "C12") (pin "2") (pinfunction "2_2") (pintype "passive"))
      (node (ref "C13") (pin "2") (pinfunction "2_2") (pintype "passive"))
      (node (ref "C14") (pin "2") (pinfunction "2_2") (pintype "passive"))
      (node (ref "C15") (pin "2") (pinfunction "2_2") (pintype "passive"))
      (node (ref "C17") (pin "2") (pinfunction "2_2") (pintype "passive"))
      (node (ref "C18") (pin "2") (pinfunction "2_2") (pintype "passive"))
      (node (ref "C19") (pin "2") (pinfunction "2_2") (pintype "passive"))
      (node (ref "C2") (pin "2") (pinfunction "2_2") (pintype "passive"))
      (node (ref "C20") (pin "-") (pinfunction "-_-") (pintype "passive"))
      (node (ref "C21") (pin "-") (pinfunction "-_-") (pintype "passive"))
      (node (ref "C22") (pin "-") (pinfunction "-_-") (pintype "passive"))
      (node (ref "C23") (pin "2") (pinfunction "2_2") (pintype "passive"))
      (node (ref "C24") (pin "2") (pinfunction "2_2") (pintype "passive"))
      (node (ref "C25") (pin "2") (pinfunction "2_2") (pintype "passive"))
      (node (ref "C26") (pin "2") (pinfunction "2_2") (pintype "passive"))
      (node (ref "C27") (pin "2") (pinfunction "2_2") (pintype "passive"))
      (node (ref "C28") (pin "2") (pinfunction "2_2") (pintype "passive"))
      (node (ref "C29") (pin "2") (pinfunction "2_2") (pintype "passive"))
      (node (ref "C3") (pin "2") (pinfunction "2_2") (pintype "passive"))
      (node (ref "C30") (pin "-") (pinfunction "-_-") (pintype "passive"))
      (node (ref "C31") (pin "-") (pinfunction "-_-") (pintype "passive"))
      (node (ref "CON1") (pin "1") (pinfunction "GND1_1") (pintype "power_in"))
      (node (ref "CON1") (pin "10") (pinfunction "A09_10") (pintype "input"))
      (node (ref "CON1") (pin "11") (pinfunction "A08_11") (pintype "input"))
      (node (ref "CON1") (pin "12") (pinfunction "A07_12") (pintype "input"))
      (node (ref "CON1") (pin "14") (pinfunction "A06_14") (pintype "input"))
      (node (ref "CON1") (pin "15") (pinfunction "A05_15") (pintype "input"))
      (node (ref "CON1") (pin "16") (pinfunction "A04_16") (pintype "input"))
      (node (ref "CON1") (pin "17") (pinfunction "A03_17") (pintype "input"))
      (node (ref "CON1") (pin "39") (pinfunction "/CSEL_39") (pintype "input"))
      (node (ref "CON1") (pin "50") (pinfunction "GND2_50") (pintype "power_in"))
      (node (ref "CON1") (pin "8") (pinfunction "A10_8") (pintype "input"))
      (node (ref "CON1") (pin "9") (pinfunction "/ATASEL_9") (pintype "input"))
      (node (ref "D1") (pin "A") (pinfunction "A_A") (pintype "passive"))
      (node (ref "IC1") (pin "15") (pinfunction "GND_15") (pintype "power_in"))
      (node (ref "IC2") (pin "15") (pinfunction "GND_15") (pintype "power_in"))
      (node (ref "IC3") (pin "16") (pinfunction "GND_16") (pintype "power_in"))
      (node (ref "IC4") (pin "4") (pinfunction "G2A_4") (pintype "input"))
      (node (ref "IC4") (pin "8") (pinfunction "GND_8") (pintype "power_in"))
      (node (ref "IC5") (pin "3") (pinfunction "GND_3") (pintype "power_in"))
      (node (ref "IC5") (pin "5") (pinfunction "~{ON}/OFF_5") (pintype "input"))
      (node (ref "IC5") (pin "6") (pinfunction "THERM_6") (pintype "bidirectional"))
      (node (ref "IC6") (pin "1") (pinfunction "DIR_1") (pintype "input"))
      (node (ref "IC6") (pin "10") (pinfunction "GND_10") (pintype "power_in"))
      (node (ref "IC6") (pin "19") (pinfunction "G_19") (pintype "input"))
      (node (ref "IC7") (pin "1") (pinfunction "DIR_1") (pintype "input"))
      (node (ref "IC7") (pin "10") (pinfunction "GND_10") (pintype "power_in"))
      (node (ref "IC7") (pin "14") (pinfunction "B5_14") (pintype "bidirectional"))
      (node (ref "IC7") (pin "15") (pinfunction "B4_15") (pintype "bidirectional"))
      (node (ref "IC7") (pin "16") (pinfunction "B3_16") (pintype "bidirectional"))
      (node (ref "IC7") (pin "17") (pinfunction "B2_17") (pintype "bidirectional"))
      (node (ref "IC7") (pin "18") (pinfunction "B1_18") (pintype "bidirectional"))
      (node (ref "IC7") (pin "19") (pinfunction "G_19") (pintype "input"))
      (node (ref "IC8") (pin "10") (pinfunction "GND_10") (pintype "power_in"))
      (node (ref "IC8") (pin "19") (pinfunction "G_19") (pintype "input"))
      (node (ref "IC8") (pin "2") (pinfunction "A1_2") (pintype "bidirectional"))
      (node (ref "IC8") (pin "3") (pinfunction "A2_3") (pintype "bidirectional"))
      (node (ref "IC8") (pin "4") (pinfunction "A3_4") (pintype "bidirectional"))
      (node (ref "JP5") (pin "1") (pinfunction "1_1") (pintype "passive"))
      (node (ref "JP7") (pin "2") (pinfunction "2_2") (pintype "passive"))
      (node (ref "JP9") (pin "10") (pinfunction "10_10") (pintype "passive"))
      (node (ref "JP9") (pin "12") (pinfunction "12_12") (pintype "passive"))
      (node (ref "JP9") (pin "14") (pinfunction "14_14") (pintype "passive"))
      (node (ref "JP9") (pin "16") (pinfunction "16_16") (pintype "passive"))
      (node (ref "JP9") (pin "18") (pinfunction "18_18") (pintype "passive"))
      (node (ref "JP9") (pin "20") (pinfunction "20_20") (pintype "passive"))
      (node (ref "JP9") (pin "22") (pinfunction "22_22") (pintype "passive"))
      (node (ref "JP9") (pin "26") (pinfunction "26_26") (pintype "passive"))
      (node (ref "R17") (pin "1") (pinfunction "1_1") (pintype "passive"))
      (node (ref "R19") (pin "1") (pinfunction "1_1") (pintype "passive"))
      (node (ref "R20") (pin "1") (pinfunction "1_1") (pintype "passive"))
      (node (ref "R9") (pin "1") (pinfunction "1_1") (pintype "passive"))
      (node (ref "U$1") (pin "15") (pinfunction "VSS_15") (pintype "bidirectional"))
      (node (ref "U$1") (pin "41") (pinfunction "VSS_41") (pintype "bidirectional"))
      (node (ref "U$1") (pin "50") (pinfunction "EV1_50") (pintype "bidirectional"))
      (node (ref "U$1") (pin "51") (pinfunction "EV2_51") (pintype "bidirectional"))
      (node (ref "U$1") (pin "67") (pinfunction "VSS_67") (pintype "bidirectional"))
      (node (ref "U$1") (pin "90") (pinfunction "VSS_90") (pintype "bidirectional"))
      (node (ref "U$2") (pin "4") (pinfunction "GND_4") (pintype "bidirectional"))
      (node (ref "U$3") (pin "2") (pinfunction "GND_2") (pintype "power_in"))
      (node (ref "U1") (pin "16") (pinfunction "VSS_16") (pintype "output"))
      (node (ref "X1") (pin "5") (pinfunction "5_5") (pintype "passive"))
      (node (ref "X2") (pin "5") (pinfunction "5_5") (pintype "passive"))
    )
    (net (code "62") (name "NO_PIN") (class "Default")
      (node (ref "JP9") (pin "24") (pinfunction "24_24") (pintype "passive"))
    )
    (net (code "63") (name "Net-(B1-PadAC1)") (class "Default")
      (node (ref "B1") (pin "AC1") (pinfunction "AC1_AC1") (pintype "passive"))
      (node (ref "F1") (pin "2") (pinfunction "2_2") (pintype "passive"))
    )
    (net (code "64") (name "Net-(CON1A-D07)") (class "Default")
      (node (ref "CON1") (pin "6") (pinfunction "D07_6") (pintype "bidirectional"))
      (node (ref "R2") (pin "1") (pinfunction "1_1") (pintype "passive"))
    )
    (net (code "65") (name "Net-(CON1A-{slash}CS1)") (class "Default")
      (node (ref "CON1") (pin "32") (pinfunction "/CS1_32") (pintype "input"))
      (node (ref "R12") (pin "1") (pinfunction "1_1") (pintype "passive"))
    )
    (net (code "66") (name "Net-(CON1A-{slash}DASP)") (class "Default")
      (node (ref "CON1") (pin "45") (pinfunction "/DASP_45") (pintype "bidirectional"))
      (node (ref "JP6") (pin "2") (pinfunction "2_2") (pintype "passive"))
    )
    (net (code "67") (name "Net-(CON1A-{slash}PDIAG)") (class "Default")
      (node (ref "CON1") (pin "46") (pinfunction "/PDIAG_46") (pintype "bidirectional"))
      (node (ref "R1") (pin "1") (pinfunction "1_1") (pintype "passive"))
    )
    (net (code "68") (name "Net-(CON1A-{slash}REG)") (class "Default")
      (node (ref "CON1") (pin "44") (pinfunction "/REG_44") (pintype "input"))
      (node (ref "R8") (pin "1") (pinfunction "1_1") (pintype "passive"))
    )
    (net (code "69") (name "Net-(CON1A-{slash}WE)") (class "Default")
      (node (ref "CON1") (pin "36") (pinfunction "/WE_36") (pintype "input"))
      (node (ref "R7") (pin "1") (pinfunction "1_1") (pintype "passive"))
    )
    (net (code "70") (name "Net-(F1-Pad1)") (class "Default")
      (node (ref "F1") (pin "1") (pinfunction "1_1") (pintype "passive"))
      (node (ref "JP8") (pin "2") (pinfunction "2_2") (pintype "passive"))
    )
    (net (code "71") (name "Net-(IC1A-C1+)") (class "Default")
      (node (ref "C4") (pin "2") (pinfunction "2_2") (pintype "passive"))
      (node (ref "IC1") (pin "1") (pinfunction "C1+_1") (pintype "bidirectional"))
    )
    (net (code "72") (name "Net-(IC1A-C1-)") (class "Default")
      (node (ref "C4") (pin "1") (pinfunction "1_1") (pintype "passive"))
      (node (ref "IC1") (pin "3") (pinfunction "C1-_3") (pintype "bidirectional"))
    )
    (net (code "73") (name "Net-(IC1A-C2+)") (class "Default")
      (node (ref "C5") (pin "2") (pinfunction "2_2") (pintype "passive"))
      (node (ref "IC1") (pin "4") (pinfunction "C2+_4") (pintype "bidirectional"))
    )
    (net (code "74") (name "Net-(IC1A-C2-)") (class "Default")
      (node (ref "C5") (pin "1") (pinfunction "1_1") (pintype "passive"))
      (node (ref "IC1") (pin "5") (pinfunction "C2-_5") (pintype "bidirectional"))
    )
    (net (code "75") (name "Net-(IC1A-R1IN)") (class "Default")
      (node (ref "IC1") (pin "13") (pinfunction "R1IN_13") (pintype "input"))
      (node (ref "X1") (pin "2") (pinfunction "2_2") (pintype "passive"))
    )
    (net (code "76") (name "Net-(IC1A-R2IN)") (class "Default")
      (node (ref "IC1") (pin "8") (pinfunction "R2IN_8") (pintype "input"))
      (node (ref "X1") (pin "8") (pinfunction "8_8") (pintype "passive"))
    )
    (net (code "77") (name "Net-(IC1A-T1OUT)") (class "Default")
      (node (ref "IC1") (pin "14") (pinfunction "T1OUT_14") (pintype "output"))
      (node (ref "X1") (pin "3") (pinfunction "3_3") (pintype "passive"))
    )
    (net (code "78") (name "Net-(IC1A-T2OUT)") (class "Default")
      (node (ref "IC1") (pin "7") (pinfunction "T2OUT_7") (pintype "output"))
      (node (ref "X1") (pin "7") (pinfunction "7_7") (pintype "passive"))
    )
    (net (code "79") (name "Net-(IC1A-V+)") (class "Default")
      (node (ref "C6") (pin "1") (pinfunction "1_1") (pintype "passive"))
      (node (ref "IC1") (pin "2") (pinfunction "V+_2") (pintype "bidirectional"))
    )
    (net (code "80") (name "Net-(IC1A-V-)") (class "Default")
      (node (ref "C25") (pin "1") (pinfunction "1_1") (pintype "passive"))
      (node (ref "IC1") (pin "6") (pinfunction "V-_6") (pintype "bidirectional"))
    )
    (net (code "81") (name "Net-(IC2A-C1+)") (class "Default")
      (node (ref "C7") (pin "2") (pinfunction "2_2") (pintype "passive"))
      (node (ref "IC2") (pin "1") (pinfunction "C1+_1") (pintype "bidirectional"))
    )
    (net (code "82") (name "Net-(IC2A-C1-)") (class "Default")
      (node (ref "C7") (pin "1") (pinfunction "1_1") (pintype "passive"))
      (node (ref "IC2") (pin "3") (pinfunction "C1-_3") (pintype "bidirectional"))
    )
    (net (code "83") (name "Net-(IC2A-C2+)") (class "Default")
      (node (ref "C8") (pin "2") (pinfunction "2_2") (pintype "passive"))
      (node (ref "IC2") (pin "4") (pinfunction "C2+_4") (pintype "bidirectional"))
    )
    (net (code "84") (name "Net-(IC2A-C2-)") (class "Default")
      (node (ref "C8") (pin "1") (pinfunction "1_1") (pintype "passive"))
      (node (ref "IC2") (pin "5") (pinfunction "C2-_5") (pintype "bidirectional"))
    )
    (net (code "85") (name "Net-(IC2A-R1IN)") (class "Default")
      (node (ref "IC2") (pin "13") (pinfunction "R1IN_13") (pintype "input"))
      (node (ref "X2") (pin "2") (pinfunction "2_2") (pintype "passive"))
    )
    (net (code "86") (name "Net-(IC2A-R2IN)") (class "Default")
      (node (ref "IC2") (pin "8") (pinfunction "R2IN_8") (pintype "input"))
      (node (ref "X2") (pin "8") (pinfunction "8_8") (pintype "passive"))
    )
    (net (code "87") (name "Net-(IC2A-T1OUT)") (class "Default")
      (node (ref "IC2") (pin "14") (pinfunction "T1OUT_14") (pintype "output"))
      (node (ref "X2") (pin "3") (pinfunction "3_3") (pintype "passive"))
    )
    (net (code "88") (name "Net-(IC2A-T2OUT)") (class "Default")
      (node (ref "IC2") (pin "7") (pinfunction "T2OUT_7") (pintype "output"))
      (node (ref "X2") (pin "7") (pinfunction "7_7") (pintype "passive"))
    )
    (net (code "89") (name "Net-(IC2A-V+)") (class "Default")
      (node (ref "C9") (pin "1") (pinfunction "1_1") (pintype "passive"))
      (node (ref "IC2") (pin "2") (pinfunction "V+_2") (pintype "bidirectional"))
    )
    (net (code "90") (name "Net-(IC2A-V-)") (class "Default")
      (node (ref "C10") (pin "1") (pinfunction "1_1") (pintype "passive"))
      (node (ref "IC2") (pin "6") (pinfunction "V-_6") (pintype "bidirectional"))
    )
    (net (code "91") (name "Net-(IC5-OUT)") (class "Default")
      (node (ref "D1") (pin "C") (pinfunction "C_C") (pintype "passive"))
      (node (ref "IC5") (pin "2") (pinfunction "OUT_2") (pintype "output"))
      (node (ref "L2") (pin "P$1") (pinfunction "1_P$1") (pintype "passive"))
    )
    (net (code "92") (name "Net-(IC5-VIN)") (class "Default")
      (node (ref "B1") (pin "+") (pinfunction "+_+") (pintype "passive"))
      (node (ref "C21") (pin "+") (pinfunction "+_+") (pintype "passive"))
      (node (ref "C23") (pin "1") (pinfunction "1_1") (pintype "passive"))
      (node (ref "IC5") (pin "1") (pinfunction "VIN_1") (pintype "input"))
    )
    (net (code "93") (name "Net-(IC8A-B4)") (class "Default")
      (node (ref "IC8") (pin "15") (pinfunction "B4_15") (pintype "bidirectional"))
      (node (ref "R23") (pin "1") (pinfunction "1_1") (pintype "passive"))
    )
    (net (code "94") (name "Net-(IC8A-B7)") (class "Default")
      (node (ref "IC8") (pin "12") (pinfunction "B7_12") (pintype "bidirectional"))
      (node (ref "R22") (pin "1") (pinfunction "1_1") (pintype "passive"))
    )
    (net (code "95") (name "Net-(IC8A-DIR)") (class "Default")
      (node (ref "IC8") (pin "1") (pinfunction "DIR_1") (pintype "input"))
      (node (ref "R11") (pin "1") (pinfunction "1_1") (pintype "passive"))
    )
    (net (code "96") (name "Net-(J2-GND)") (class "Default")
      (node (ref "B1") (pin "AC2") (pinfunction "AC2_AC2") (pintype "passive"))
      (node (ref "J2") (pin "GND@1") (pinfunction "GNDBREAK_GND@1") (pintype "bidirectional"))
      (node (ref "J2") (pin "GND@2") (pinfunction "GND_GND@2") (pintype "bidirectional"))
    )
    (net (code "97") (name "Net-(J2-PadPWR)") (class "Default")
      (node (ref "J2") (pin "PWR") (pinfunction "PWR_PWR") (pintype "bidirectional"))
      (node (ref "JP8") (pin "1") (pinfunction "1_1") (pintype "passive"))
    )
    (net (code "98") (name "Net-(JP6-Pad1)") (class "Default")
      (node (ref "JP6") (pin "1") (pinfunction "1_1") (pintype "passive"))
      (node (ref "R13") (pin "1") (pinfunction "1_1") (pintype "passive"))
    )
    (net (code "99") (name "Net-(U$1-ST)") (class "Default")
      (node (ref "R14") (pin "1") (pinfunction "1_1") (pintype "passive"))
      (node (ref "U$1") (pin "1") (pinfunction "ST_1") (pintype "bidirectional"))
    )
    (net (code "100") (name "Net-(U$1-{slash}DREQ1)") (class "Default")
      (node (ref "R15") (pin "1") (pinfunction "1_1") (pintype "passive"))
      (node (ref "U$1") (pin "45") (pinfunction "/DREQ1_45") (pintype "bidirectional"))
    )
    (net (code "101") (name "Net-(U$2-CT)") (class "Default")
      (node (ref "C18") (pin "1") (pinfunction "1_1") (pintype "passive"))
      (node (ref "U$2") (pin "3") (pinfunction "CT_3") (pintype "bidirectional"))
    )
    (net (code "102") (name "Net-(U$2-REF)") (class "Default")
      (node (ref "C19") (pin "1") (pinfunction "1_1") (pintype "passive"))
      (node (ref "U$2") (pin "1") (pinfunction "REF_1") (pintype "bidirectional"))
    )
    (net (code "103") (name "Net-(U$2-RESET)") (class "Default")
      (node (ref "R9") (pin "2") (pinfunction "2_2") (pintype "passive"))
      (node (ref "U$2") (pin "6") (pinfunction "RESET_6") (pintype "bidirectional"))
    )
    (net (code "104") (name "Net-(U$2-~{RESIN})") (class "Default")
      (node (ref "JP5") (pin "2") (pinfunction "2_2") (pintype "passive"))
      (node (ref "R10") (pin "1") (pinfunction "1_1") (pintype "passive"))
      (node (ref "U$2") (pin "2") (pinfunction "~{RESIN}_2") (pintype "bidirectional"))
    )
    (net (code "105") (name "OSC_IN") (class "Default")
      (node (ref "U$1") (pin "92") (pinfunction "EXTAL_92") (pintype "bidirectional"))
      (node (ref "U$3") (pin "3") (pinfunction "OUT_3") (pintype "output"))
    )
    (net (code "106") (name "PD0") (class "Default")
      (node (ref "IC6") (pin "2") (pinfunction "A1_2") (pintype "bidirectional"))
      (node (ref "JP9") (pin "3") (pinfunction "3_3") (pintype "passive"))
    )
    (net (code "107") (name "PD0_IN") (class "Default")
      (node (ref "IC6") (pin "18") (pinfunction "B1_18") (pintype "bidirectional"))
      (node (ref "U$1") (pin "52") (pinfunction "PA0/HD0_52") (pintype "bidirectional"))
    )
    (net (code "108") (name "PD1") (class "Default")
      (node (ref "IC6") (pin "3") (pinfunction "A2_3") (pintype "bidirectional"))
      (node (ref "JP9") (pin "5") (pinfunction "5_5") (pintype "passive"))
    )
    (net (code "109") (name "PD1_IN") (class "Default")
      (node (ref "IC6") (pin "17") (pinfunction "B2_17") (pintype "bidirectional"))
      (node (ref "U$1") (pin "53") (pinfunction "PA1/HD1_53") (pintype "bidirectional"))
    )
    (net (code "110") (name "PD2") (class "Default")
      (node (ref "IC6") (pin "4") (pinfunction "A3_4") (pintype "bidirectional"))
      (node (ref "JP9") (pin "7") (pinfunction "7_7") (pintype "passive"))
    )
    (net (code "111") (name "PD2_IN") (class "Default")
      (node (ref "IC6") (pin "16") (pinfunction "B3_16") (pintype "bidirectional"))
      (node (ref "U$1") (pin "54") (pinfunction "PA2/HD2_54") (pintype "bidirectional"))
    )
    (net (code "112") (name "PD3") (class "Default")
      (node (ref "IC6") (pin "5") (pinfunction "A4_5") (pintype "bidirectional"))
      (node (ref "JP9") (pin "9") (pinfunction "9_9") (pintype "passive"))
    )
    (net (code "113") (name "PD3_IN") (class "Default")
      (node (ref "IC6") (pin "15") (pinfunction "B4_15") (pintype "bidirectional"))
      (node (ref "U$1") (pin "55") (pinfunction "PA3/HD3_55") (pintype "bidirectional"))
    )
    (net (code "114") (name "PD4") (class "Default")
      (node (ref "IC6") (pin "6") (pinfunction "A5_6") (pintype "bidirectional"))
      (node (ref "JP9") (pin "11") (pinfunction "11_11") (pintype "passive"))
    )
    (net (code "115") (name "PD4_IN") (class "Default")
      (node (ref "IC6") (pin "14") (pinfunction "B5_14") (pintype "bidirectional"))
      (node (ref "U$1") (pin "56") (pinfunction "PA4/HD4_56") (pintype "bidirectional"))
    )
    (net (code "116") (name "PD5") (class "Default")
      (node (ref "IC6") (pin "7") (pinfunction "A6_7") (pintype "bidirectional"))
      (node (ref "JP9") (pin "13") (pinfunction "13_13") (pintype "passive"))
    )
    (net (code "117") (name "PD5_IN") (class "Default")
      (node (ref "IC6") (pin "13") (pinfunction "B6_13") (pintype "bidirectional"))
      (node (ref "U$1") (pin "57") (pinfunction "PA5/HD5_57") (pintype "bidirectional"))
    )
    (net (code "118") (name "PD6") (class "Default")
      (node (ref "IC6") (pin "8") (pinfunction "A7_8") (pintype "bidirectional"))
      (node (ref "JP9") (pin "15") (pinfunction "15_15") (pintype "passive"))
    )
    (net (code "119") (name "PD6_IN") (class "Default")
      (node (ref "IC6") (pin "12") (pinfunction "B7_12") (pintype "bidirectional"))
      (node (ref "U$1") (pin "58") (pinfunction "PA6/HD6_58") (pintype "bidirectional"))
    )
    (net (code "120") (name "PD7") (class "Default")
      (node (ref "IC6") (pin "9") (pinfunction "A8_9") (pintype "bidirectional"))
      (node (ref "JP9") (pin "17") (pinfunction "17_17") (pintype "passive"))
    )
    (net (code "121") (name "PD7_IN") (class "Default")
      (node (ref "IC6") (pin "11") (pinfunction "B8_11") (pintype "bidirectional"))
      (node (ref "U$1") (pin "59") (pinfunction "PA7/HD7_59") (pintype "bidirectional"))
    )
    (net (code "122") (name "PE") (class "Default")
      (node (ref "IC8") (pin "7") (pinfunction "A6_7") (pintype "bidirectional"))
      (node (ref "JP9") (pin "23") (pinfunction "23_23") (pintype "passive"))
      (node (ref "R19") (pin "2") (pinfunction "2_2") (pintype "passive"))
    )
    (net (code "123") (name "PE_OUT") (class "Default")
      (node (ref "IC8") (pin "13") (pinfunction "B6_13") (pintype "bidirectional"))
      (node (ref "U$1") (pin "34") (pinfunction "/DCD0/PB2_34") (pintype "bidirectional"))
    )
    (net (code "124") (name "PR_ACK_OUT") (class "Default")
      (node (ref "IC8") (pin "11") (pinfunction "B8_11") (pintype "bidirectional"))
      (node (ref "U$1") (pin "36") (pinfunction "RXA0/PB4_36") (pintype "bidirectional"))
    )
    (net (code "125") (name "RTS1") (class "Default")
      (node (ref "IC2") (pin "10") (pinfunction "T2IN_10") (pintype "input"))
      (node (ref "U$1") (pin "62") (pinfunction "/MWR/PC2//RTSA_62") (pintype "bidirectional"))
    )
    (net (code "126") (name "RTS2") (class "Default")
      (node (ref "IC1") (pin "10") (pinfunction "T2IN_10") (pintype "input"))
      (node (ref "U$1") (pin "47") (pinfunction "/TEND1//RTSB//HRXRDY_47") (pintype "bidirectional"))
    )
    (net (code "127") (name "RX") (class "Default")
      (node (ref "JP11") (pin "1") (pinfunction "1_1") (pintype "passive"))
    )
    (net (code "128") (name "RXD1") (class "Default")
      (node (ref "IC2") (pin "12") (pinfunction "R1OUT_12") (pintype "output"))
      (node (ref "U$1") (pin "71") (pinfunction "RXDA_71") (pintype "bidirectional"))
    )
    (net (code "129") (name "RXD2") (class "Default")
      (node (ref "IC1") (pin "12") (pinfunction "R1OUT_12") (pintype "output"))
      (node (ref "U$1") (pin "78") (pinfunction "RXDB/HA1_78") (pintype "bidirectional"))
    )
    (net (code "130") (name "SLCT") (class "Default")
      (node (ref "IC8") (pin "6") (pinfunction "A5_6") (pintype "bidirectional"))
      (node (ref "JP9") (pin "25") (pinfunction "25_25") (pintype "passive"))
      (node (ref "R17") (pin "2") (pinfunction "2_2") (pintype "passive"))
    )
    (net (code "131") (name "SLCT_OUT") (class "Default")
      (node (ref "IC8") (pin "14") (pinfunction "B5_14") (pintype "bidirectional"))
      (node (ref "U$1") (pin "33") (pinfunction "/CTS0/PB1_33") (pintype "bidirectional"))
    )
    (net (code "132") (name "TX") (class "Default")
      (node (ref "JP11") (pin "2") (pinfunction "2_2") (pintype "passive"))
    )
    (net (code "133") (name "TXD1") (class "Default")
      (node (ref "IC2") (pin "11") (pinfunction "T1IN_11") (pintype "input"))
      (node (ref "U$1") (pin "73") (pinfunction "TXDA_73") (pintype "bidirectional"))
    )
    (net (code "134") (name "TXD2") (class "Default")
      (node (ref "IC1") (pin "11") (pinfunction "T1IN_11") (pintype "input"))
      (node (ref "U$1") (pin "76") (pinfunction "TXDB//HDDIS_76") (pintype "bidirectional"))
    )
    (net (code "135") (name "unconnected-(CON1A-D08-Pad47)") (class "Default")
      (node (ref "CON1") (pin "47") (pinfunction "D08_47") (pintype "bidirectional"))
    )
    (net (code "136") (name "unconnected-(CON1A-D09-Pad48)") (class "Default")
      (node (ref "CON1") (pin "48") (pinfunction "D09_48") (pintype "bidirectional"))
    )
    (net (code "137") (name "unconnected-(CON1A-D10-Pad49)") (class "Default")
      (node (ref "CON1") (pin "49") (pinfunction "D10_49") (pintype "bidirectional"))
    )
    (net (code "138") (name "unconnected-(CON1A-D11-Pad27)") (class "Default")
      (node (ref "CON1") (pin "27") (pinfunction "D11_27") (pintype "bidirectional"))
    )
    (net (code "139") (name "unconnected-(CON1A-D12-Pad28)") (class "Default")
      (node (ref "CON1") (pin "28") (pinfunction "D12_28") (pintype "bidirectional"))
    )
    (net (code "140") (name "unconnected-(CON1A-D13-Pad29)") (class "Default")
      (node (ref "CON1") (pin "29") (pinfunction "D13_29") (pintype "bidirectional"))
    )
    (net (code "141") (name "unconnected-(CON1A-D14-Pad30)") (class "Default")
      (node (ref "CON1") (pin "30") (pinfunction "D14_30") (pintype "bidirectional"))
    )
    (net (code "142") (name "unconnected-(CON1A-D15-Pad31)") (class "Default")
      (node (ref "CON1") (pin "31") (pinfunction "D15_31") (pintype "bidirectional"))
    )
    (net (code "143") (name "unconnected-(CON1A-INTRQ-Pad37)") (class "Default")
      (node (ref "CON1") (pin "37") (pinfunction "INTRQ_37") (pintype "output"))
    )
    (net (code "144") (name "unconnected-(CON1A-IORDY-Pad42)") (class "Default")
      (node (ref "CON1") (pin "42") (pinfunction "IORDY_42") (pintype "output"))
    )
    (net (code "145") (name "unconnected-(CON1A-{slash}CD1-Pad26)") (class "Default")
      (node (ref "CON1") (pin "26") (pinfunction "/CD1_26") (pintype "output"))
    )
    (net (code "146") (name "unconnected-(CON1A-{slash}CD2-Pad25)") (class "Default")
      (node (ref "CON1") (pin "25") (pinfunction "/CD2_25") (pintype "output"))
    )
    (net (code "147") (name "unconnected-(CON1A-{slash}INPACK-Pad43)") (class "Default")
      (node (ref "CON1") (pin "43") (pinfunction "/INPACK_43") (pintype "output"))
    )
    (net (code "148") (name "unconnected-(CON1A-{slash}IOCS16-Pad24)") (class "Default")
      (node (ref "CON1") (pin "24") (pinfunction "/IOCS16_24") (pintype "output"))
    )
    (net (code "149") (name "unconnected-(CON1A-{slash}VS1-Pad33)") (class "Default")
      (node (ref "CON1") (pin "33") (pinfunction "/VS1_33") (pintype "output"))
    )
    (net (code "150") (name "unconnected-(CON1A-{slash}VS2-Pad40)") (class "Default")
      (node (ref "CON1") (pin "40") (pinfunction "/VS2_40") (pintype "output"))
    )
    (net (code "151") (name "unconnected-(IC7A-A1-Pad2)") (class "Default")
      (node (ref "IC7") (pin "2") (pinfunction "A1_2") (pintype "bidirectional"))
    )
    (net (code "152") (name "unconnected-(IC7A-A2-Pad3)") (class "Default")
      (node (ref "IC7") (pin "3") (pinfunction "A2_3") (pintype "bidirectional"))
    )
    (net (code "153") (name "unconnected-(IC7A-A3-Pad4)") (class "Default")
      (node (ref "IC7") (pin "4") (pinfunction "A3_4") (pintype "bidirectional"))
    )
    (net (code "154") (name "unconnected-(IC7A-A4-Pad5)") (class "Default")
      (node (ref "IC7") (pin "5") (pinfunction "A4_5") (pintype "bidirectional"))
    )
    (net (code "155") (name "unconnected-(IC7A-A5-Pad6)") (class "Default")
      (node (ref "IC7") (pin "6") (pinfunction "A5_6") (pintype "bidirectional"))
    )
    (net (code "156") (name "unconnected-(IC8A-B1-Pad18)") (class "Default")
      (node (ref "IC8") (pin "18") (pinfunction "B1_18") (pintype "bidirectional"))
    )
    (net (code "157") (name "unconnected-(IC8A-B2-Pad17)") (class "Default")
      (node (ref "IC8") (pin "17") (pinfunction "B2_17") (pintype "bidirectional"))
    )
    (net (code "158") (name "unconnected-(IC8A-B3-Pad16)") (class "Default")
      (node (ref "IC8") (pin "16") (pinfunction "B3_16") (pintype "bidirectional"))
    )
    (net (code "159") (name "unconnected-(JP2-Pad7)") (class "Default")
      (node (ref "JP2") (pin "7") (pinfunction "7_7") (pintype "passive"))
    )
    (net (code "160") (name "unconnected-(JP2-Pad8)") (class "Default")
      (node (ref "JP2") (pin "8") (pinfunction "8_8") (pintype "passive"))
    )
    (net (code "161") (name "unconnected-(U$1-CKA0{slash}{slash}DREQ0-Pad40)") (class "Default")
      (node (ref "U$1") (pin "40") (pinfunction "CKA0//DREQ0_40") (pintype "bidirectional"))
    )
    (net (code "162") (name "unconnected-(U$1-CKA1{slash}{slash}TEND0-Pad42)") (class "Default")
      (node (ref "U$1") (pin "42") (pinfunction "CKA1//TEND0_42") (pintype "bidirectional"))
    )
    (net (code "163") (name "unconnected-(U$1-CKS{slash}{slash}W{slash}{slash}REQB{slash}{slash}HTXRDY-Pad44)") (class "Default")
      (node (ref "U$1") (pin "44") (pinfunction "CKS//W//REQB//HTXRDY_44") (pintype "bidirectional"))
    )
    (net (code "164") (name "unconnected-(U$1-E-Pad85)") (class "Default")
      (node (ref "U$1") (pin "85") (pinfunction "E_85") (pintype "bidirectional"))
    )
    (net (code "165") (name "unconnected-(U$1-IEI-Pad69)") (class "Default")
      (node (ref "U$1") (pin "69") (pinfunction "IEI_69") (pintype "bidirectional"))
    )
    (net (code "166") (name "unconnected-(U$1-TRXCA-Pad72)") (class "Default")
      (node (ref "U$1") (pin "72") (pinfunction "TRXCA_72") (pintype "bidirectional"))
    )
    (net (code "167") (name "unconnected-(U$1-TXS{slash}{slash}DTR{slash}{slash}REQB{slash}HINTR-Pad43)") (class "Default")
      (node (ref "U$1") (pin "43") (pinfunction "TXS//DTR//REQB/HINTR_43") (pintype "bidirectional"))
    )
    (net (code "168") (name "unconnected-(U$1-XTAL-Pad91)") (class "Default")
      (node (ref "U$1") (pin "91") (pinfunction "XTAL_91") (pintype "bidirectional"))
    )
    (net (code "169") (name "unconnected-(U$1-{slash}DCDA{slash}PC0-Pad64)") (class "Default")
      (node (ref "U$1") (pin "64") (pinfunction "/DCDA/PC0_64") (pintype "bidirectional"))
    )
    (net (code "170") (name "unconnected-(U$1-{slash}DCDB{slash}{slash}HRD-Pad74)") (class "Default")
      (node (ref "U$1") (pin "74") (pinfunction "/DCDB//HRD_74") (pintype "bidirectional"))
    )
    (net (code "171") (name "unconnected-(U$1-{slash}DTR{slash}{slash}REQA{slash}PC3-Pad61)") (class "Default")
      (node (ref "U$1") (pin "61") (pinfunction "/DTR//REQA/PC3_61") (pintype "bidirectional"))
    )
    (net (code "172") (name "unconnected-(U$1-{slash}IOCS{slash}IEO-Pad68)") (class "Default")
      (node (ref "U$1") (pin "68") (pinfunction "/IOCS/IEO_68") (pintype "bidirectional"))
    )
    (net (code "173") (name "unconnected-(U$1-{slash}MRD{slash}{slash}MREQ-Pad84)") (class "Default")
      (node (ref "U$1") (pin "84") (pinfunction "/MRD//MREQ_84") (pintype "bidirectional"))
    )
    (net (code "174") (name "unconnected-(U$1-{slash}RTXCA-Pad66)") (class "Default")
      (node (ref "U$1") (pin "66") (pinfunction "/RTXCA_66") (pintype "bidirectional"))
    )
    (net (code "175") (name "unconnected-(U$1-{slash}RTXCB{slash}HA2-Pad79)") (class "Default")
      (node (ref "U$1") (pin "79") (pinfunction "/RTXCB/HA2_79") (pintype "bidirectional"))
    )
    (net (code "176") (name "unconnected-(U$1-{slash}SYNCA{slash}PC4-Pad65)") (class "Default")
      (node (ref "U$1") (pin "65") (pinfunction "/SYNCA/PC4_65") (pintype "bidirectional"))
    )
    (net (code "177") (name "unconnected-(U$1-{slash}SYNCB{slash}{slash}HCS-Pad80)") (class "Default")
      (node (ref "U$1") (pin "80") (pinfunction "/SYNCB//HCS_80") (pintype "bidirectional"))
    )
    (net (code "178") (name "unconnected-(U$1-{slash}TRXCB{slash}HA0-Pad77)") (class "Default")
      (node (ref "U$1") (pin "77") (pinfunction "/TRXCB/HA0_77") (pintype "bidirectional"))
    )
    (net (code "179") (name "unconnected-(U$1-{slash}W{slash}{slash}REQA{slash}PC5-Pad60)") (class "Default")
      (node (ref "U$1") (pin "60") (pinfunction "/W//REQA/PC5_60") (pintype "bidirectional"))
    )
    (net (code "180") (name "unconnected-(U$3-TRI-Pad1)") (class "Default")
      (node (ref "U$3") (pin "1") (pinfunction "TRI_1") (pintype "input"))
    )
    (net (code "181") (name "unconnected-(X1-Pad1)") (class "Default")
      (node (ref "X1") (pin "1") (pinfunction "1_1") (pintype "passive"))
    )
    (net (code "182") (name "unconnected-(X1-Pad4)") (class "Default")
      (node (ref "X1") (pin "4") (pinfunction "4_4") (pintype "passive"))
    )
    (net (code "183") (name "unconnected-(X1-Pad6)") (class "Default")
      (node (ref "X1") (pin "6") (pinfunction "6_6") (pintype "passive"))
    )
    (net (code "184") (name "unconnected-(X1-Pad9)") (class "Default")
      (node (ref "X1") (pin "9") (pinfunction "9_9") (pintype "passive"))
    )
    (net (code "185") (name "unconnected-(X2-Pad1)") (class "Default")
      (node (ref "X2") (pin "1") (pinfunction "1_1") (pintype "passive"))
    )
    (net (code "186") (name "unconnected-(X2-Pad4)") (class "Default")
      (node (ref "X2") (pin "4") (pinfunction "4_4") (pintype "passive"))
    )
    (net (code "187") (name "unconnected-(X2-Pad6)") (class "Default")
      (node (ref "X2") (pin "6") (pinfunction "6_6") (pintype "passive"))
    )
    (net (code "188") (name "unconnected-(X2-Pad9)") (class "Default")
      (node (ref "X2") (pin "9") (pinfunction "9_9") (pintype "passive"))
    )
    (net (code "189") (name "{slash}ACK") (class "Default")
      (node (ref "IC8") (pin "9") (pinfunction "A8_9") (pintype "bidirectional"))
      (node (ref "JP9") (pin "19") (pinfunction "19_19") (pintype "passive"))
      (node (ref "R21") (pin "1") (pinfunction "1_1") (pintype "passive"))
    )
    (net (code "190") (name "{slash}AFD") (class "Default")
      (node (ref "JP9") (pin "2") (pinfunction "2_2") (pintype "passive"))
    )
    (net (code "191") (name "{slash}ERR") (class "Default")
      (node (ref "IC8") (pin "5") (pinfunction "A4_5") (pintype "bidirectional"))
      (node (ref "JP9") (pin "4") (pinfunction "4_4") (pintype "passive"))
      (node (ref "R16") (pin "1") (pinfunction "1_1") (pintype "passive"))
    )
    (net (code "192") (name "{slash}ERR_OUT") (class "Default")
      (node (ref "R23") (pin "2") (pinfunction "2_2") (pintype "passive"))
      (node (ref "U$1") (pin "32") (pinfunction "/RTS0/PB0_32") (pintype "bidirectional"))
    )
    (net (code "193") (name "{slash}INIT") (class "Default")
      (node (ref "IC7") (pin "8") (pinfunction "A7_8") (pintype "bidirectional"))
      (node (ref "JP9") (pin "6") (pinfunction "6_6") (pintype "passive"))
    )
    (net (code "194") (name "{slash}PRINTER_INIT_IN") (class "Default")
      (node (ref "IC7") (pin "12") (pinfunction "B7_12") (pintype "bidirectional"))
      (node (ref "U$1") (pin "38") (pinfunction "RXA1/PB6_38") (pintype "bidirectional"))
    )
    (net (code "195") (name "{slash}PSTB") (class "Default")
      (node (ref "IC7") (pin "9") (pinfunction "A8_9") (pintype "bidirectional"))
      (node (ref "JP9") (pin "1") (pinfunction "1_1") (pintype "passive"))
    )
    (net (code "196") (name "{slash}PSTB_IN") (class "Default")
      (node (ref "IC7") (pin "11") (pinfunction "B8_11") (pintype "bidirectional"))
      (node (ref "U$1") (pin "39") (pinfunction "RXS//CTS1/PB7_39") (pintype "bidirectional"))
    )
    (net (code "197") (name "{slash}SLIN") (class "Default")
      (node (ref "IC7") (pin "7") (pinfunction "A6_7") (pintype "bidirectional"))
      (node (ref "JP9") (pin "8") (pinfunction "8_8") (pintype "passive"))
    )
    (net (code "198") (name "{slash}SLIN_IN") (class "Default")
      (node (ref "IC7") (pin "13") (pinfunction "B6_13") (pintype "bidirectional"))
      (node (ref "U$1") (pin "37") (pinfunction "TXA1/PB5_37") (pintype "bidirectional"))
    )
  )
)
